# Display.net
KiCad netlist of a schematic drawn in Altium Designer
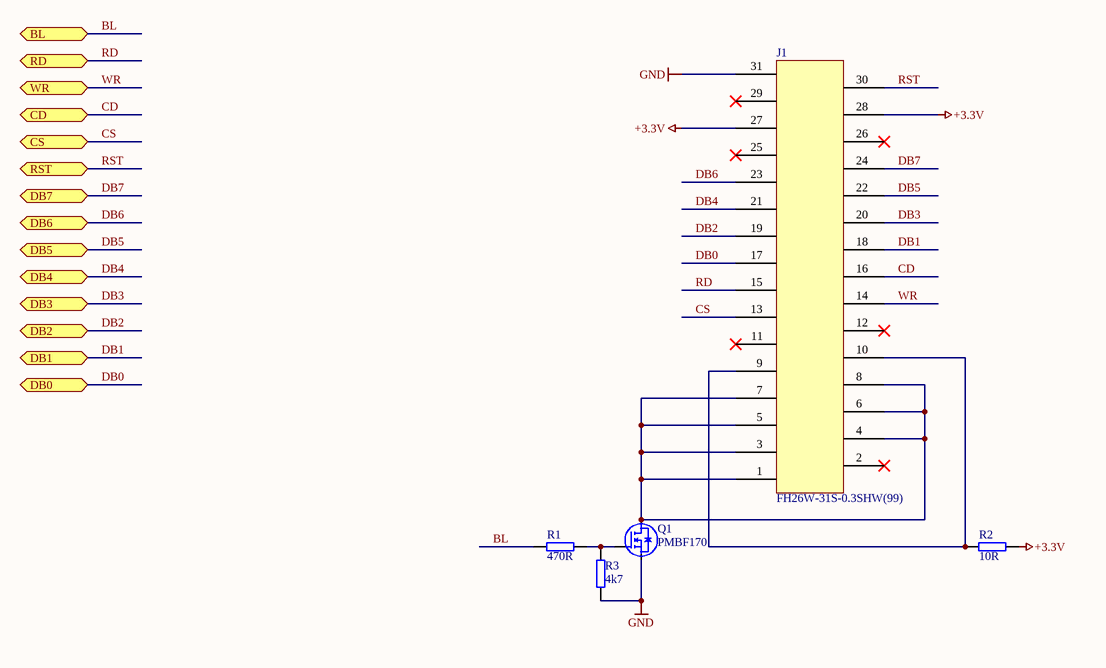
[diagram p0: Display.SchDoc]

(export (version "E")
  (design (tool "Eeschema 10.0.6"))
  (components
    (comp (ref "J1")
      (value "FH26W-31S-0.3SHW(99)")
      (footprint "FH26W-31S-0.3SHW(99)")
      (description "Hirose FH26 0.3mm Pitch 31 Way Right Angle SMT Female FPC Connector, ZIF Bottom Contact")
      (fields (field (name "MANUFACTURER") "Hirose"))
      (libsource (lib "SCH_LIB") (part "FH26W-31S-0.3SHW(99)"))
    )
    (comp (ref "Q1")
      (value "PMBF170")
      (footprint "SOT23")
      (description "N-Channel MOSFET")
      (libsource (lib "SCH_LIB") (part "PMBF170"))
    )
    (comp (ref "R1")
      (value "470R")
      (footprint "RES 0805")
      (description "RESISTOR")
      (libsource (lib "SCH_LIB") (part "RES"))
    )
    (comp (ref "R2")
      (value "10R")
      (footprint "RES 0805")
      (description "RESISTOR")
      (libsource (lib "") (part "RES_2"))
    )
    (comp (ref "R3")
      (value "4k7")
      (footprint "RES 0805")
      (description "RESISTOR")
      (libsource (lib "") (part "RES_1"))
    )
  )
  (nets
    (net (code "1") (name "+3.3V") (class "Default")
      (node (ref "J1") (pin "27") (pinfunction "27_27") (pintype "passive"))
      (node (ref "J1") (pin "28") (pinfunction "28_28") (pintype "passive"))
      (node (ref "R2") (pin "1") (pinfunction "1_1") (pintype "passive"))
    )
    (net (code "2") (name "/BL") (class "Default")
      (node (ref "R1") (pin "1") (pinfunction "1_1") (pintype "passive"))
    )
    (net (code "3") (name "/CD") (class "Default")
      (node (ref "J1") (pin "16") (pinfunction "16_16") (pintype "passive"))
    )
    (net (code "4") (name "/CS") (class "Default")
      (node (ref "J1") (pin "13") (pinfunction "13_13") (pintype "passive"))
    )
    (net (code "5") (name "/DB0") (class "Default")
      (node (ref "J1") (pin "17") (pinfunction "17_17") (pintype "passive"))
    )
    (net (code "6") (name "/DB1") (class "Default")
      (node (ref "J1") (pin "18") (pinfunction "18_18") (pintype "passive"))
    )
    (net (code "7") (name "/DB2") (class "Default")
      (node (ref "J1") (pin "19") (pinfunction "19_19") (pintype "passive"))
    )
    (net (code "8") (name "/DB3") (class "Default")
      (node (ref "J1") (pin "20") (pinfunction "20_20") (pintype "passive"))
    )
    (net (code "9") (name "/DB4") (class "Default")
      (node (ref "J1") (pin "21") (pinfunction "21_21") (pintype "passive"))
    )
    (net (code "10") (name "/DB5") (class "Default")
      (node (ref "J1") (pin "22") (pinfunction "22_22") (pintype "passive"))
    )
    (net (code "11") (name "/DB6") (class "Default")
      (node (ref "J1") (pin "23") (pinfunction "23_23") (pintype "passive"))
    )
    (net (code "12") (name "/DB7") (class "Default")
      (node (ref "J1") (pin "24") (pinfunction "24_24") (pintype "passive"))
    )
    (net (code "13") (name "/RD") (class "Default")
      (node (ref "J1") (pin "15") (pinfunction "15_15") (pintype "passive"))
    )
    (net (code "14") (name "/RST") (class "Default")
      (node (ref "J1") (pin "30") (pinfunction "30_30") (pintype "passive"))
    )
    (net (code "15") (name "/WR") (class "Default")
      (node (ref "J1") (pin "14") (pinfunction "14_14") (pintype "passive"))
    )
    (net (code "16") (name "GND") (class "Default")
      (node (ref "J1") (pin "31") (pinfunction "31_31") (pintype "passive"))
      (node (ref "Q1") (pin "2") (pinfunction "S_2") (pintype "passive"))
      (node (ref "R3") (pin "1") (pinfunction "1_1") (pintype "passive"))
    )
    (net (code "17") (name "Net-(J1-Pad10)") (class "Default")
      (node (ref "J1") (pin "10") (pinfunction "10_10") (pintype "passive"))
      (node (ref "J1") (pin "9") (pinfunction "9_9") (pintype "passive"))
      (node (ref "R2") (pin "2") (pinfunction "2_2") (pintype "passive"))
    )
    (net (code "18") (name "Net-(Q1-D)") (class "Default")
      (node (ref "J1") (pin "1") (pinfunction "1_1") (pintype "passive"))
      (node (ref "J1") (pin "3") (pinfunction "3_3") (pintype "passive"))
      (node (ref "J1") (pin "4") (pinfunction "4_4") (pintype "passive"))
      (node (ref "J1") (pin "5") (pinfunction "5_5") (pintype "passive"))
      (node (ref "J1") (pin "6") (pinfunction "6_6") (pintype "passive"))
      (node (ref "J1") (pin "7") (pinfunction "7_7") (pintype "passive"))
      (node (ref "J1") (pin "8") (pinfunction "8_8") (pintype "passive"))
      (node (ref "Q1") (pin "3") (pinfunction "D_3") (pintype "passive"))
    )
    (net (code "19") (name "Net-(Q1-G)") (class "Default")
      (node (ref "Q1") (pin "1") (pinfunction "G_1") (pintype "passive"))
      (node (ref "R1") (pin "2") (pinfunction "2_2") (pintype "passive"))
      (node (ref "R3") (pin "2") (pinfunction "2_2") (pintype "passive"))
    )
    (net (code "20") (name "unconnected-(J1-Pad2)") (class "Default")
      (node (ref "J1") (pin "2") (pinfunction "2_2") (pintype "passive+no_connect"))
    )
    (net (code "21") (name "unconnected-(J1-Pad11)") (class "Default")
      (node (ref "J1") (pin "11") (pinfunction "11_11") (pintype "passive+no_connect"))
    )
    (net (code "22") (name "unconnected-(J1-Pad12)") (class "Default")
      (node (ref "J1") (pin "12") (pinfunction "12_12") (pintype "passive+no_connect"))
    )
    (net (code "23") (name "unconnected-(J1-Pad25)") (class "Default")
      (node (ref "J1") (pin "25") (pinfunction "25_25") (pintype "passive+no_connect"))
    )
    (net (code "24") (name "unconnected-(J1-Pad26)") (class "Default")
      (node (ref "J1") (pin "26") (pinfunction "26_26") (pintype "passive+no_connect"))
    )
    (net (code "25") (name "unconnected-(J1-Pad29)") (class "Default")
      (node (ref "J1") (pin "29") (pinfunction "29_29") (pintype "passive+no_connect"))
    )
  )
)
